# rrsdc.net
KiCad netlist of a schematic drawn in EAGLE
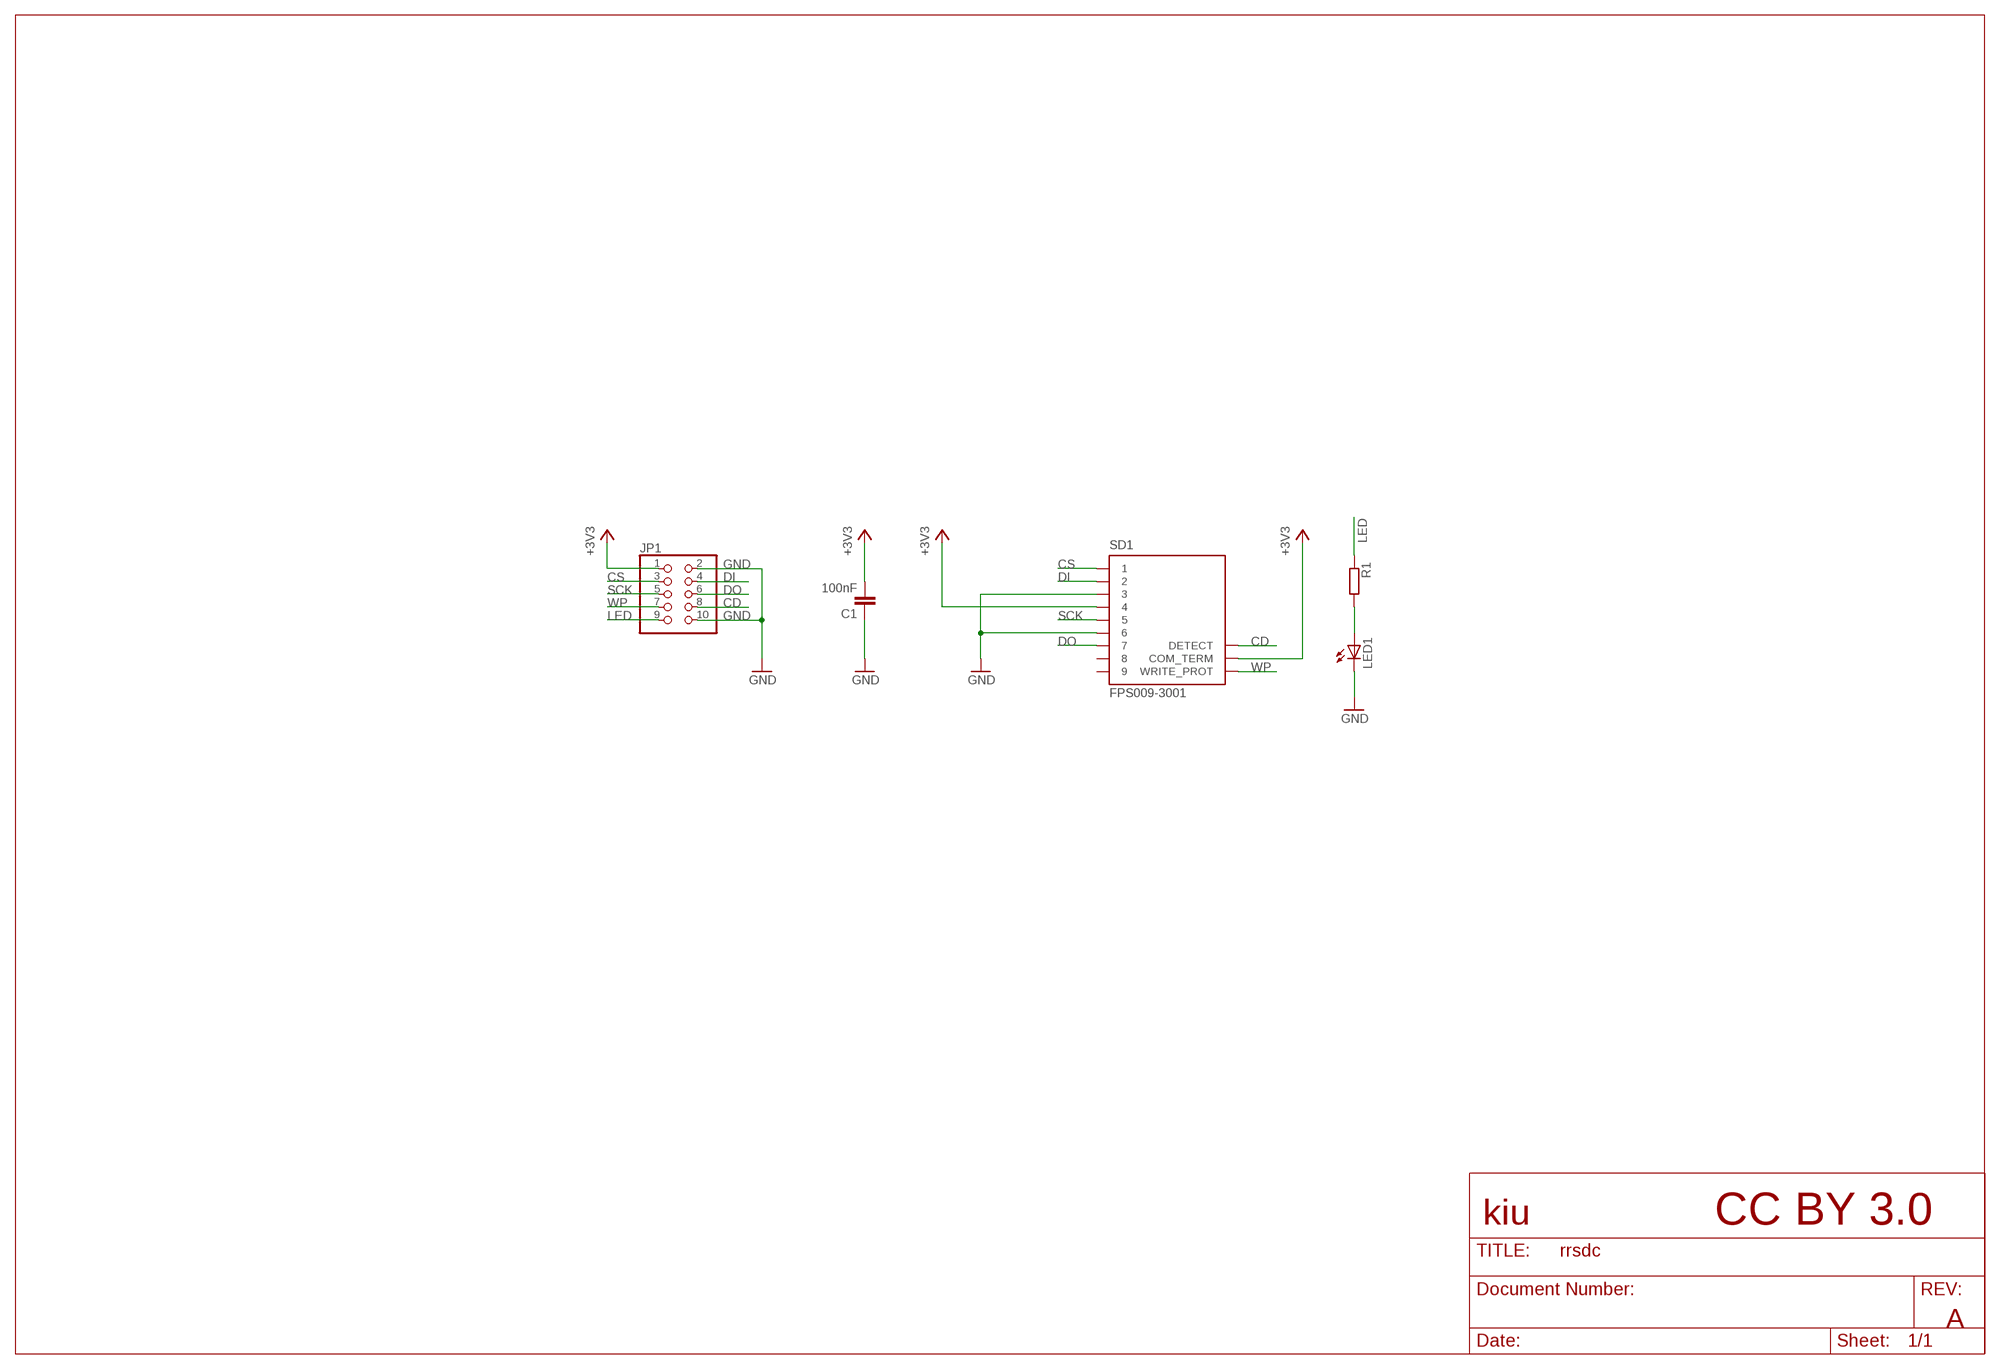
[diagram p0: schematic, sheet 1]

(export (version "E")
  (design (tool "Eeschema 10.0.6"))
  (components
    (comp (ref "C1")
      (value "100nF")
      (footprint "eagle-import:C0805")
      (libsource (lib "eagle-import") (part "C-EUC0805"))
    )
    (comp (ref "JP1")
      (value "PINHD-2X5")
      (footprint "eagle-import:2X05")
      (libsource (lib "eagle-import") (part "PINHD-2X5"))
    )
    (comp (ref "LED1")
      (value "SIDELEDPLCC-NOTHERM")
      (footprint "eagle-import:PLCC-2-NOTHERM")
      (libsource (lib "eagle-import") (part "SIDELEDPLCC-NOTHERM"))
    )
    (comp (ref "R1")
      (value "R-EU_R0805")
      (footprint "eagle-import:R0805")
      (libsource (lib "eagle-import") (part "R-EU_R0805"))
    )
    (comp (ref "SD1")
      (value "FPS009-3001")
      (footprint "eagle-import:FPS009-3000")
      (fields (field (name "MPN") "FPS009-3001-BL"))
      (libsource (lib "eagle-import") (part "FPS009-3001"))
    )
  )
  (nets
    (net (code "1") (name "+3V3") (class "Default")
      (node (ref "C1") (pin "2") (pinfunction "2_2") (pintype "passive"))
      (node (ref "JP1") (pin "1") (pinfunction "1_1") (pintype "passive"))
      (node (ref "SD1") (pin "4") (pinfunction "4_4") (pintype "input"))
      (node (ref "SD1") (pin "COM_TERM") (pinfunction "COM_TERM_COM_TERM") (pintype "input"))
    )
    (net (code "2") (name "/CD") (class "Default")
      (node (ref "JP1") (pin "8") (pinfunction "8_8") (pintype "passive"))
      (node (ref "SD1") (pin "DETECT") (pinfunction "DETECT_DETECT") (pintype "input"))
    )
    (net (code "3") (name "/CS") (class "Default")
      (node (ref "JP1") (pin "3") (pinfunction "3_3") (pintype "passive"))
      (node (ref "SD1") (pin "1") (pinfunction "1_1") (pintype "input"))
    )
    (net (code "4") (name "/DI") (class "Default")
      (node (ref "JP1") (pin "4") (pinfunction "4_4") (pintype "passive"))
      (node (ref "SD1") (pin "2") (pinfunction "2_2") (pintype "input"))
    )
    (net (code "5") (name "/DO") (class "Default")
      (node (ref "JP1") (pin "6") (pinfunction "6_6") (pintype "passive"))
      (node (ref "SD1") (pin "7") (pinfunction "7_7") (pintype "input"))
    )
    (net (code "6") (name "/LED") (class "Default")
      (node (ref "JP1") (pin "9") (pinfunction "9_9") (pintype "passive"))
      (node (ref "R1") (pin "1") (pinfunction "1_1") (pintype "passive"))
    )
    (net (code "7") (name "/SCK") (class "Default")
      (node (ref "JP1") (pin "5") (pinfunction "5_5") (pintype "passive"))
      (node (ref "SD1") (pin "5") (pinfunction "5_5") (pintype "input"))
    )
    (net (code "8") (name "/WP") (class "Default")
      (node (ref "JP1") (pin "7") (pinfunction "7_7") (pintype "passive"))
      (node (ref "SD1") (pin "WRITE_PROT") (pinfunction "WRITE_PROT_WRITE_PROT") (pintype "input"))
    )
    (net (code "9") (name "GND") (class "Default")
      (node (ref "C1") (pin "1") (pinfunction "1_1") (pintype "passive"))
      (node (ref "JP1") (pin "10") (pinfunction "10_10") (pintype "passive"))
      (node (ref "JP1") (pin "2") (pinfunction "2_2") (pintype "passive"))
      (node (ref "LED1") (pin "C") (pinfunction "C_C") (pintype "passive"))
      (node (ref "SD1") (pin "3") (pinfunction "3_3") (pintype "input"))
      (node (ref "SD1") (pin "6") (pinfunction "6_6") (pintype "input"))
    )
    (net (code "10") (name "Net-(LED1-PadA)") (class "Default")
      (node (ref "LED1") (pin "A") (pinfunction "A_A") (pintype "passive"))
      (node (ref "R1") (pin "2") (pinfunction "2_2") (pintype "passive"))
    )
    (net (code "11") (name "unconnected-(SD1-Pad8)") (class "Default")
      (node (ref "SD1") (pin "8") (pinfunction "8_8") (pintype "input"))
    )
    (net (code "12") (name "unconnected-(SD1-Pad9)") (class "Default")
      (node (ref "SD1") (pin "9") (pinfunction "9_9") (pintype "input"))
    )
  )
)
